# Headers.net
KiCad netlist of a schematic drawn in Altium Designer
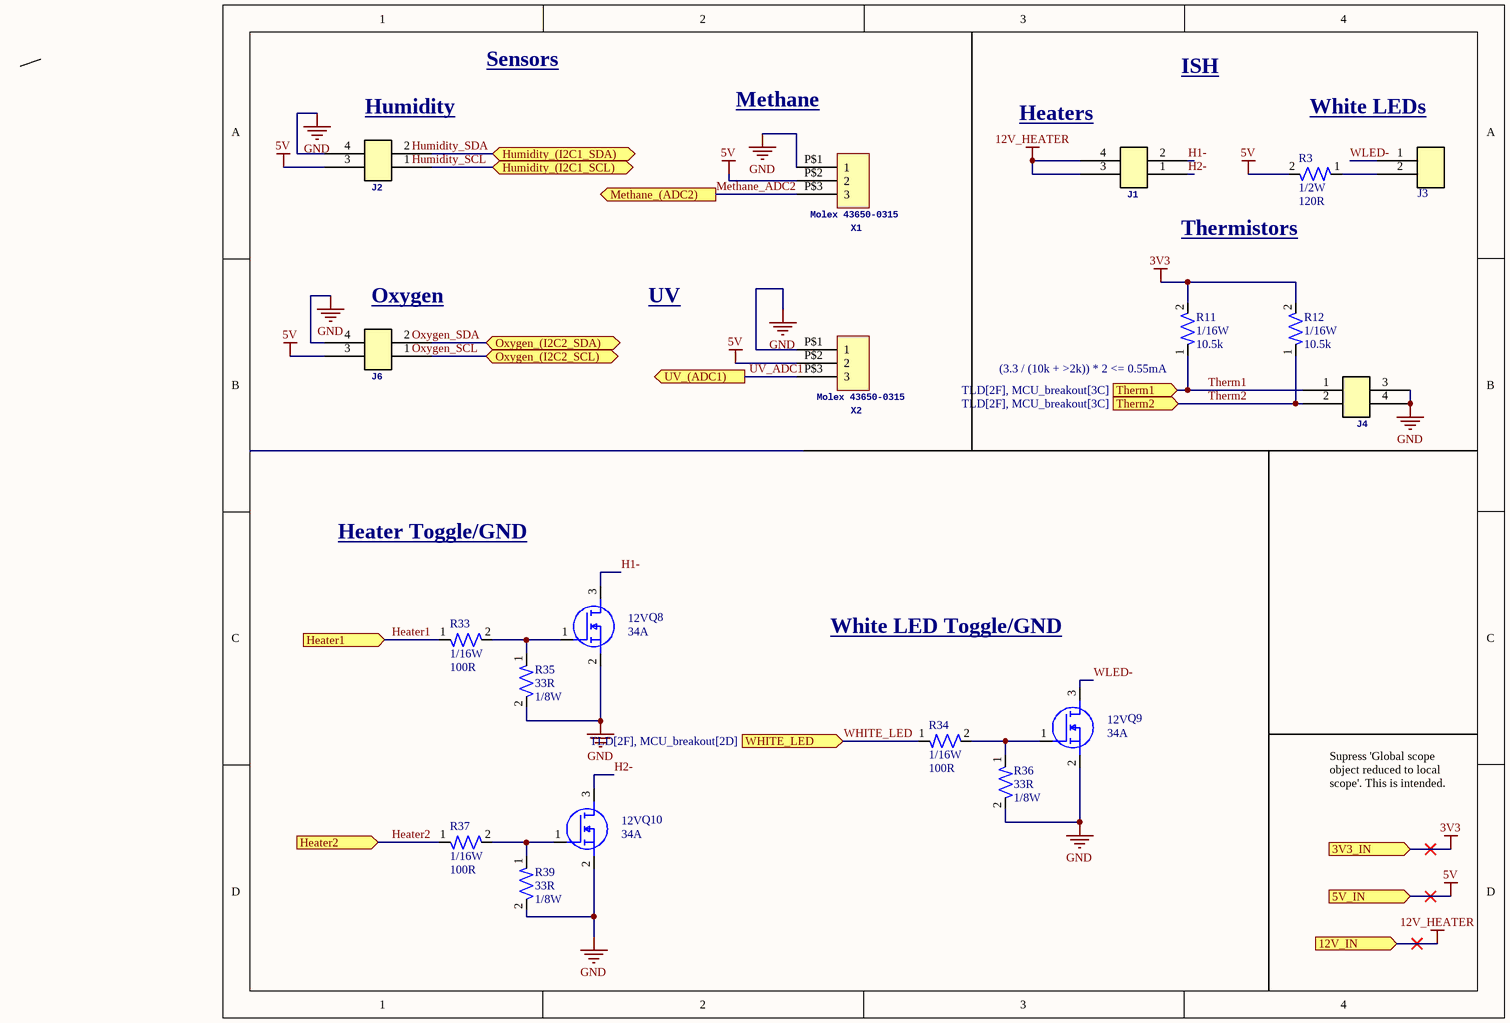
[diagram p0: Headers.SchDoc]

(export (version "E")
  (design (tool "Eeschema 10.0.6"))
  (components
    (comp (ref "J1")
      (value "Molex 43045-0412")
      (footprint "CONN-4POS-0002")
      (description "CONN HEADER VERT 4POS 3MM")
      (libsource (lib "JLC_25") (part "CONN-4POS-0002"))
    )
    (comp (ref "J2")
      (value "Molex 43045-0412")
      (footprint "CONN-4POS-0002")
      (description "CONN HEADER VERT 4POS 3MM")
      (libsource (lib "JLC_25") (part "CONN-4POS-0002"))
    )
    (comp (ref "J3")
      (value "0430450212")
      (footprint "CONN-2POS-0001")
      (description "CONN HEADER VERT 2POS")
      (libsource (lib "JLC_25") (part "CONN-2POS-0001"))
    )
    (comp (ref "J4")
      (value "Molex 43045-0412")
      (footprint "CONN-4POS-0002")
      (description "CONN HEADER VERT 4POS 3MM")
      (libsource (lib "") (part "CONN-4POS-0002_1"))
    )
    (comp (ref "J6")
      (value "Molex 43045-0412")
      (footprint "CONN-4POS-0002")
      (description "CONN HEADER VERT 4POS 3MM")
      (libsource (lib "JLC_25") (part "CONN-4POS-0002"))
    )
    (comp (ref "Q8")
      (value "SI4838BDY-T1-GE3")
      (footprint "SOIC8_NARROW_VIS")
      (description "MOSFET N-CH 12 V 34A (Tc) 2.5W (Ta), 5.7W (Tc) Surface Mount 8-SOIC")
      (libsource (lib "JLC_25") (part "NMOS-34A-0001"))
    )
    (comp (ref "Q9")
      (value "SI4838BDY-T1-GE3")
      (footprint "SOIC8_NARROW_VIS")
      (description "MOSFET N-CH 12 V 34A (Tc) 2.5W (Ta), 5.7W (Tc) Surface Mount 8-SOIC")
      (libsource (lib "JLC_25") (part "NMOS-34A-0001"))
    )
    (comp (ref "Q10")
      (value "SI4838BDY-T1-GE3")
      (footprint "SOIC8_NARROW_VIS")
      (description "MOSFET N-CH 12 V 34A (Tc) 2.5W (Ta), 5.7W (Tc) Surface Mount 8-SOIC")
      (libsource (lib "JLC_25") (part "NMOS-34A-0001"))
    )
    (comp (ref "R3")
      (value "RC1210FR-07120RL")
      (footprint "RES-1210")
      (description "RES 120 OHM 1% 1/2W 1210")
      (fields
        (field (name "TOLERANCE") "1%")
        (field (name "POWER") "1/2W")
        (field (name "RESISTANCE") "120R")
      )
      (libsource (lib "JLC_25") (part "RES-120-0001"))
    )
    (comp (ref "R11")
      (value "RC0402FR-0710K5L")
      (footprint "RES-0402")
      (description "RES 10.5K OHM 1% 1/16W 0402")
      (fields
        (field (name "TOLERANCE") "1%")
        (field (name "POWER") "1/16W")
        (field (name "RESISTANCE") "10.5k")
      )
      (libsource (lib "JLC_25") (part "RES-10.5k-0001"))
    )
    (comp (ref "R12")
      (value "RC0402FR-0710K5L")
      (footprint "RES-0402")
      (description "RES 10.5K OHM 1% 1/16W 0402")
      (fields
        (field (name "TOLERANCE") "1%")
        (field (name "POWER") "1/16W")
        (field (name "RESISTANCE") "10.5k")
      )
      (libsource (lib "JLC_25") (part "RES-10.5k-0001"))
    )
    (comp (ref "R33")
      (value "RC0402FR-07100RL")
      (footprint "RES-0402")
      (description "RES 100 OHM 1% 1/16W 0402")
      (fields
        (field (name "TOLERANCE") "1%")
        (field (name "POWER") "1/16W")
        (field (name "RESISTANCE") "100R")
      )
      (libsource (lib "JLC_25") (part "RES-100-0001"))
    )
    (comp (ref "R34")
      (value "RC0402FR-07100RL")
      (footprint "RES-0402")
      (description "RES 100 OHM 1% 1/16W 0402")
      (fields
        (field (name "TOLERANCE") "1%")
        (field (name "POWER") "1/16W")
        (field (name "RESISTANCE") "100R")
      )
      (libsource (lib "JLC_25") (part "RES-100-0001"))
    )
    (comp (ref "R35")
      (value "RC0402FR-7W33RL")
      (footprint "RES-0402")
      (description "RES 33 OHM 1% 1/8W 0402")
      (fields (field (name "TOLERANCE") "1%") (field (name "RESISTANCE") "33R") (field (name "POWER") "1/8W"))
      (libsource (lib "JLC_25") (part "RES-33-0001"))
    )
    (comp (ref "R36")
      (value "RC0402FR-7W33RL")
      (footprint "RES-0402")
      (description "RES 33 OHM 1% 1/8W 0402")
      (fields (field (name "TOLERANCE") "1%") (field (name "RESISTANCE") "33R") (field (name "POWER") "1/8W"))
      (libsource (lib "JLC_25") (part "RES-33-0001"))
    )
    (comp (ref "R37")
      (value "RC0402FR-07100RL")
      (footprint "RES-0402")
      (description "RES 100 OHM 1% 1/16W 0402")
      (fields
        (field (name "TOLERANCE") "1%")
        (field (name "POWER") "1/16W")
        (field (name "RESISTANCE") "100R")
      )
      (libsource (lib "JLC_25") (part "RES-100-0001"))
    )
    (comp (ref "R39")
      (value "RC0402FR-7W33RL")
      (footprint "RES-0402")
      (description "RES 33 OHM 1% 1/8W 0402")
      (fields (field (name "TOLERANCE") "1%") (field (name "RESISTANCE") "33R") (field (name "POWER") "1/8W"))
      (libsource (lib "JLC_25") (part "RES-33-0001"))
    )
    (comp (ref "X1")
      (value "Molex 43650-0315")
      (footprint "43650-0315")
      (libsource (lib "JLC_25") (part "Micro-Fit Molex 3 Pin Vertical"))
    )
    (comp (ref "X2")
      (value "Molex 43650-0315")
      (footprint "43650-0315")
      (libsource (lib "JLC_25") (part "Micro-Fit Molex 3 Pin Vertical"))
    )
  )
  (nets
    (net (code "1") (name "/H1-") (class "Default")
      (node (ref "J1") (pin "2") (pinfunction "2_2") (pintype "passive"))
      (node (ref "Q8") (pin "3") (pinfunction "D_3") (pintype "passive"))
    )
    (net (code "2") (name "/H2-") (class "Default")
      (node (ref "J1") (pin "1") (pinfunction "1_1") (pintype "passive"))
      (node (ref "Q10") (pin "3") (pinfunction "D_3") (pintype "passive"))
    )
    (net (code "3") (name "/Heater1") (class "Default")
      (node (ref "R33") (pin "1") (pinfunction "1_1") (pintype "passive"))
    )
    (net (code "4") (name "/Heater2") (class "Default")
      (node (ref "R37") (pin "1") (pinfunction "1_1") (pintype "passive"))
    )
    (net (code "5") (name "/Humidity_(I2C1_SCL)") (class "Default")
      (node (ref "J2") (pin "1") (pinfunction "1_1") (pintype "passive"))
    )
    (net (code "6") (name "/Humidity_(I2C1_SDA)") (class "Default")
      (node (ref "J2") (pin "2") (pinfunction "2_2") (pintype "passive"))
    )
    (net (code "9") (name "/Methane_ADC2") (class "Default")
      (node (ref "X1") (pin "P$3") (pinfunction "3_P$3") (pintype "passive"))
    )
    (net (code "10") (name "/Oxygen_(I2C2_SCL)") (class "Default")
      (node (ref "J6") (pin "1") (pinfunction "1_1") (pintype "passive"))
    )
    (net (code "11") (name "/Oxygen_(I2C2_SDA)") (class "Default")
      (node (ref "J6") (pin "2") (pinfunction "2_2") (pintype "passive"))
    )
    (net (code "14") (name "/Therm1") (class "Default")
      (node (ref "J4") (pin "1") (pinfunction "1_1") (pintype "passive"))
      (node (ref "R11") (pin "1") (pinfunction "1_1") (pintype "passive"))
    )
    (net (code "15") (name "/Therm2") (class "Default")
      (node (ref "J4") (pin "2") (pinfunction "2_2") (pintype "passive"))
      (node (ref "R12") (pin "1") (pinfunction "1_1") (pintype "passive"))
    )
    (net (code "16") (name "/UV_ADC1") (class "Default")
      (node (ref "X2") (pin "P$3") (pinfunction "3_P$3") (pintype "passive"))
    )
    (net (code "17") (name "/WHITE_LED") (class "Default")
      (node (ref "R34") (pin "1") (pinfunction "1_1") (pintype "passive"))
    )
    (net (code "18") (name "/WLED-") (class "Default")
      (node (ref "J3") (pin "1") (pinfunction "7_1") (pintype "passive"))
      (node (ref "Q9") (pin "3") (pinfunction "D_3") (pintype "passive"))
    )
    (net (code "19") (name "3V3") (class "Default")
      (node (ref "R11") (pin "2") (pinfunction "2_2") (pintype "passive"))
      (node (ref "R12") (pin "2") (pinfunction "2_2") (pintype "passive"))
    )
    (net (code "20") (name "5V") (class "Default")
      (node (ref "J2") (pin "3") (pinfunction "3_3") (pintype "passive"))
      (node (ref "J6") (pin "3") (pinfunction "3_3") (pintype "passive"))
      (node (ref "R3") (pin "2") (pinfunction "2_2") (pintype "passive"))
      (node (ref "X1") (pin "P$2") (pinfunction "2_P$2") (pintype "passive"))
      (node (ref "X2") (pin "P$2") (pinfunction "2_P$2") (pintype "passive"))
    )
    (net (code "21") (name "12V_HEATER") (class "Default")
      (node (ref "J1") (pin "3") (pinfunction "3_3") (pintype "passive"))
      (node (ref "J1") (pin "4") (pinfunction "4_4") (pintype "passive"))
    )
    (net (code "22") (name "GND") (class "Default")
      (node (ref "J2") (pin "4") (pinfunction "4_4") (pintype "passive"))
      (node (ref "J4") (pin "3") (pinfunction "3_3") (pintype "passive"))
      (node (ref "J4") (pin "4") (pinfunction "4_4") (pintype "passive"))
      (node (ref "J6") (pin "4") (pinfunction "4_4") (pintype "passive"))
      (node (ref "Q10") (pin "2") (pinfunction "S_2") (pintype "passive"))
      (node (ref "Q8") (pin "2") (pinfunction "S_2") (pintype "passive"))
      (node (ref "Q9") (pin "2") (pinfunction "S_2") (pintype "passive"))
      (node (ref "R35") (pin "2") (pinfunction "2_2") (pintype "passive"))
      (node (ref "R36") (pin "2") (pinfunction "2_2") (pintype "passive"))
      (node (ref "R39") (pin "2") (pinfunction "2_2") (pintype "passive"))
      (node (ref "X1") (pin "P$1") (pinfunction "1_P$1") (pintype "passive"))
      (node (ref "X2") (pin "P$1") (pinfunction "1_P$1") (pintype "passive"))
    )
    (net (code "23") (name "Net-(J3-8)") (class "Default")
      (node (ref "J3") (pin "2") (pinfunction "8_2") (pintype "passive"))
      (node (ref "R3") (pin "1") (pinfunction "1_1") (pintype "passive"))
    )
    (net (code "24") (name "Net-(Q8-G)") (class "Default")
      (node (ref "Q8") (pin "1") (pinfunction "G_1") (pintype "passive"))
      (node (ref "R33") (pin "2") (pinfunction "2_2") (pintype "passive"))
      (node (ref "R35") (pin "1") (pinfunction "1_1") (pintype "passive"))
    )
    (net (code "25") (name "Net-(Q9-G)") (class "Default")
      (node (ref "Q9") (pin "1") (pinfunction "G_1") (pintype "passive"))
      (node (ref "R34") (pin "2") (pinfunction "2_2") (pintype "passive"))
      (node (ref "R36") (pin "1") (pinfunction "1_1") (pintype "passive"))
    )
    (net (code "26") (name "Net-(Q10-G)") (class "Default")
      (node (ref "Q10") (pin "1") (pinfunction "G_1") (pintype "passive"))
      (node (ref "R37") (pin "2") (pinfunction "2_2") (pintype "passive"))
      (node (ref "R39") (pin "1") (pinfunction "1_1") (pintype "passive"))
    )
  )
)
